# dmx-transciever.net
KiCad netlist of a schematic drawn in EAGLE
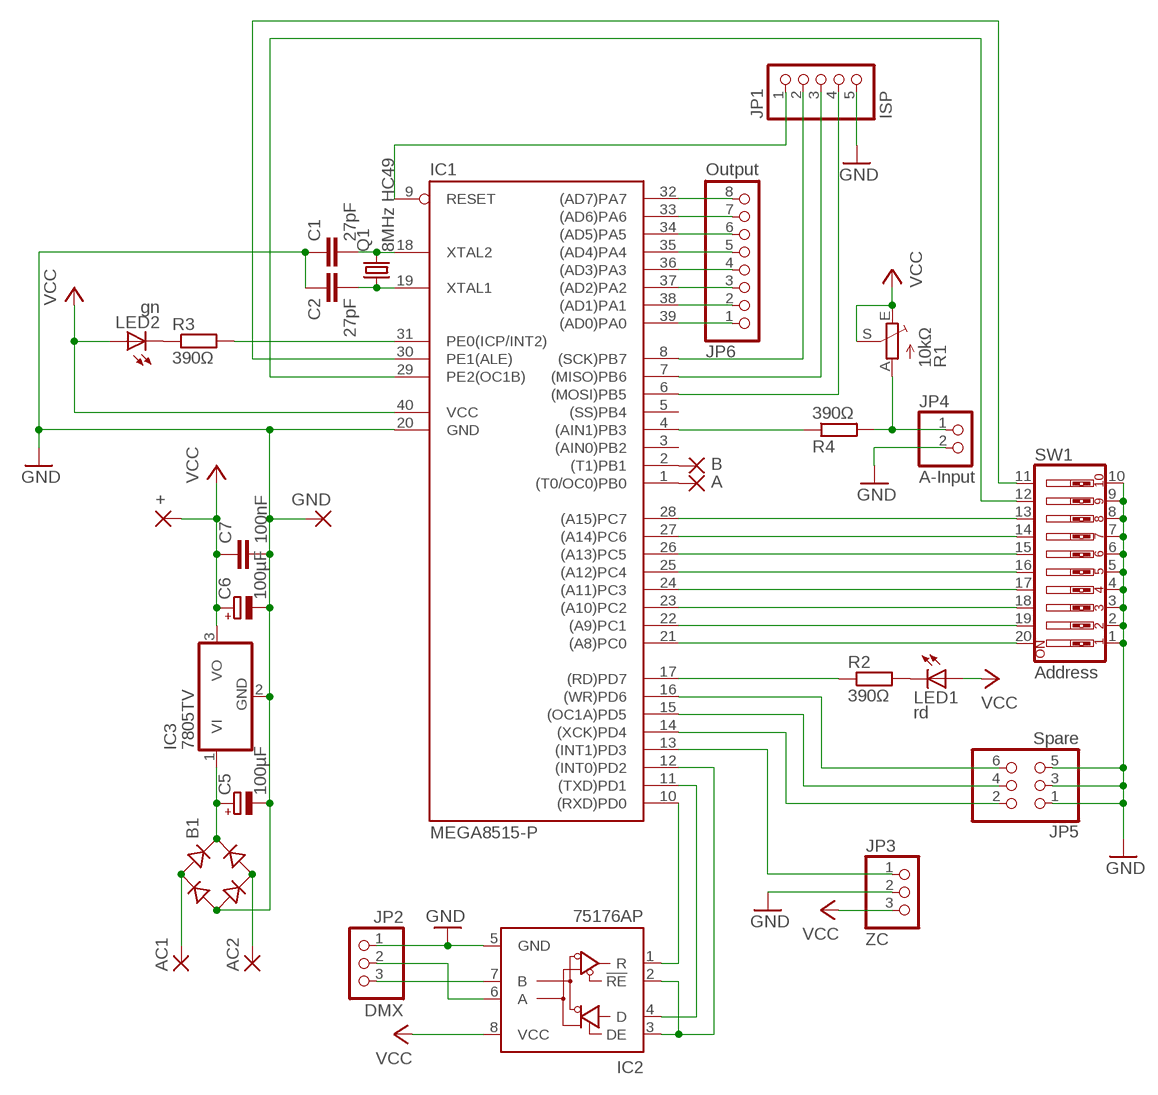
[diagram p0: schematic, sheet 1]

(export (version "E")
  (design (tool "Eeschema 10.0.6"))
  (components
    (comp (ref "+")
      (value "WIREPAD2,54/1,0")
      (footprint "eagle-import:2,54_1,0")
      (libsource (lib "eagle-import") (part "WIREPAD2,54/1,0"))
    )
    (comp (ref "A")
      (value "WIREPAD2,54/1,0")
      (footprint "eagle-import:2,54_1,0")
      (libsource (lib "eagle-import") (part "WIREPAD2,54/1,0"))
    )
    (comp (ref "AC1")
      (value "WIREPAD2,54/1,0")
      (footprint "eagle-import:2,54_1,0")
      (libsource (lib "eagle-import") (part "WIREPAD2,54/1,0"))
    )
    (comp (ref "AC2")
      (value "WIREPAD2,54/1,0")
      (footprint "eagle-import:2,54_1,0")
      (libsource (lib "eagle-import") (part "WIREPAD2,54/1,0"))
    )
    (comp (ref "B")
      (value "WIREPAD2,54/1,0")
      (footprint "eagle-import:2,54_1,0")
      (libsource (lib "eagle-import") (part "WIREPAD2,54/1,0"))
    )
    (comp (ref "B1")
      (value "RB1A")
      (footprint "eagle-import:RB1A")
      (libsource (lib "eagle-import") (part "RB1A"))
    )
    (comp (ref "C1")
      (value "27pF")
      (footprint "eagle-import:C050-024X044")
      (libsource (lib "eagle-import") (part "C-EU050-024X044"))
    )
    (comp (ref "C2")
      (value "27pF")
      (footprint "eagle-import:C050-024X044")
      (libsource (lib "eagle-import") (part "C-EU050-024X044"))
    )
    (comp (ref "C5")
      (value "100µF")
      (footprint "eagle-import:E2,5-7")
      (libsource (lib "eagle-import") (part "CPOL-EUE2.5-7"))
    )
    (comp (ref "C6")
      (value "100µF")
      (footprint "eagle-import:E2,5-7")
      (libsource (lib "eagle-import") (part "CPOL-EUE2.5-7"))
    )
    (comp (ref "C7")
      (value "100nF")
      (footprint "eagle-import:C050-024X044")
      (libsource (lib "eagle-import") (part "C-EU050-024X044"))
    )
    (comp (ref "GND")
      (value "WIREPAD2,54/1,0")
      (footprint "eagle-import:2,54_1,0")
      (libsource (lib "eagle-import") (part "WIREPAD2,54/1,0"))
    )
    (comp (ref "IC1")
      (value "MEGA8515-P")
      (footprint "eagle-import:DIL40")
      (libsource (lib "eagle-import") (part "MEGA8515-P"))
    )
    (comp (ref "IC2")
      (value "75176AP")
      (footprint "eagle-import:DIL08")
      (libsource (lib "eagle-import") (part "75176AP"))
    )
    (comp (ref "IC3")
      (value "7805TV")
      (footprint "eagle-import:TO220V")
      (libsource (lib "eagle-import") (part "78TV05"))
    )
    (comp (ref "JP1")
      (value "ISP")
      (footprint "eagle-import:1X05")
      (libsource (lib "eagle-import") (part "PINHD-1X5"))
    )
    (comp (ref "JP2")
      (value "DMX")
      (footprint "eagle-import:1X03")
      (libsource (lib "eagle-import") (part "PINHD-1X3"))
    )
    (comp (ref "JP3")
      (value "ZC")
      (footprint "eagle-import:1X03")
      (libsource (lib "eagle-import") (part "PINHD-1X3"))
    )
    (comp (ref "JP4")
      (value "A-Input")
      (footprint "eagle-import:1X02")
      (libsource (lib "eagle-import") (part "PINHD-1X2"))
    )
    (comp (ref "JP5")
      (value "Spare")
      (footprint "eagle-import:2X03")
      (libsource (lib "eagle-import") (part "PINHD-2X3"))
    )
    (comp (ref "JP6")
      (value "Output")
      (footprint "eagle-import:1X08")
      (libsource (lib "eagle-import") (part "PINHD-1X8"))
    )
    (comp (ref "LED1")
      (value "rd")
      (footprint "eagle-import:LED3MM")
      (fields (field (name "MF") "VISHAY SEMICONDUCTOR"))
      (libsource (lib "eagle-import") (part "TLLR4400"))
    )
    (comp (ref "LED2")
      (value "gn")
      (footprint "eagle-import:LED3MM")
      (fields (field (name "MF") "VISHAY SEMICONDUCTOR"))
      (libsource (lib "eagle-import") (part "TLLG4400"))
    )
    (comp (ref "Q1")
      (value "8MHz HC49")
      (footprint "eagle-import:HC49_S")
      (libsource (lib "eagle-import") (part "CRYSTALHC49S"))
    )
    (comp (ref "R1")
      (value "10kΩ")
      (footprint "eagle-import:PT-10S")
      (libsource (lib "eagle-import") (part "TRIM_EU-PT10S"))
    )
    (comp (ref "R2")
      (value "390Ω")
      (footprint "eagle-import:0207_10")
      (libsource (lib "eagle-import") (part "R-EU_0207/10"))
    )
    (comp (ref "R3")
      (value "390Ω")
      (footprint "eagle-import:0309V")
      (libsource (lib "eagle-import") (part "R-EU_0309/V"))
    )
    (comp (ref "R4")
      (value "390Ω")
      (footprint "eagle-import:0207_10")
      (libsource (lib "eagle-import") (part "R-EU_0207/10"))
    )
    (comp (ref "SW1")
      (value "Address")
      (footprint "eagle-import:EDG-10")
      (libsource (lib "eagle-import") (part "SW_DIP-10"))
    )
  )
  (nets
    (net (code "1") (name "GND") (class "Default")
      (node (ref "B1") (pin "-") (pinfunction "-_-") (pintype "passive"))
      (node (ref "C1") (pin "1") (pinfunction "1_1") (pintype "passive"))
      (node (ref "C2") (pin "1") (pinfunction "1_1") (pintype "passive"))
      (node (ref "C5") (pin "-") (pinfunction "-_-") (pintype "passive"))
      (node (ref "C6") (pin "-") (pinfunction "-_-") (pintype "passive"))
      (node (ref "C7") (pin "2") (pinfunction "2_2") (pintype "passive"))
      (node (ref "GND") (pin "1") (pinfunction "P_1") (pintype "passive"))
      (node (ref "IC1") (pin "20") (pinfunction "GND_20") (pintype "power_in"))
      (node (ref "IC2") (pin "5") (pinfunction "GND_5") (pintype "power_in"))
      (node (ref "IC3") (pin "2") (pinfunction "GND_2") (pintype "passive"))
      (node (ref "JP1") (pin "5") (pinfunction "5_5") (pintype "passive"))
      (node (ref "JP2") (pin "1") (pinfunction "1_1") (pintype "passive"))
      (node (ref "JP3") (pin "2") (pinfunction "2_2") (pintype "passive"))
      (node (ref "JP4") (pin "2") (pinfunction "2_2") (pintype "passive"))
      (node (ref "JP5") (pin "1") (pinfunction "1_1") (pintype "passive"))
      (node (ref "JP5") (pin "3") (pinfunction "3_3") (pintype "passive"))
      (node (ref "JP5") (pin "5") (pinfunction "5_5") (pintype "passive"))
      (node (ref "SW1") (pin "1") (pinfunction "1_1") (pintype "passive"))
      (node (ref "SW1") (pin "10") (pinfunction "10_10") (pintype "passive"))
      (node (ref "SW1") (pin "2") (pinfunction "2_2") (pintype "passive"))
      (node (ref "SW1") (pin "3") (pinfunction "3_3") (pintype "passive"))
      (node (ref "SW1") (pin "4") (pinfunction "4_4") (pintype "passive"))
      (node (ref "SW1") (pin "5") (pinfunction "5_5") (pintype "passive"))
      (node (ref "SW1") (pin "6") (pinfunction "6_6") (pintype "passive"))
      (node (ref "SW1") (pin "7") (pinfunction "7_7") (pintype "passive"))
      (node (ref "SW1") (pin "8") (pinfunction "8_8") (pintype "passive"))
      (node (ref "SW1") (pin "9") (pinfunction "9_9") (pintype "passive"))
    )
    (net (code "2") (name "Net-(A-P)") (class "Default")
      (node (ref "A") (pin "1") (pinfunction "P_1") (pintype "passive"))
      (node (ref "IC1") (pin "1") (pinfunction "(T0/OC0)PB0_1") (pintype "bidirectional"))
    )
    (net (code "3") (name "Net-(AC1-P)") (class "Default")
      (node (ref "AC1") (pin "1") (pinfunction "P_1") (pintype "passive"))
      (node (ref "B1") (pin "AC1") (pinfunction "AC1_AC1") (pintype "passive"))
    )
    (net (code "4") (name "Net-(AC2-P)") (class "Default")
      (node (ref "AC2") (pin "1") (pinfunction "P_1") (pintype "passive"))
      (node (ref "B1") (pin "AC2") (pinfunction "AC2_AC2") (pintype "passive"))
    )
    (net (code "5") (name "Net-(B-P)") (class "Default")
      (node (ref "B") (pin "1") (pinfunction "P_1") (pintype "passive"))
      (node (ref "IC1") (pin "2") (pinfunction "(T1)PB1_2") (pintype "bidirectional"))
    )
    (net (code "6") (name "Net-(IC1-(A8)PC0)") (class "Default")
      (node (ref "IC1") (pin "21") (pinfunction "(A8)PC0_21") (pintype "bidirectional"))
      (node (ref "SW1") (pin "20") (pinfunction "20_20") (pintype "passive"))
    )
    (net (code "7") (name "Net-(IC1-(A9)PC1)") (class "Default")
      (node (ref "IC1") (pin "22") (pinfunction "(A9)PC1_22") (pintype "bidirectional"))
      (node (ref "SW1") (pin "19") (pinfunction "19_19") (pintype "passive"))
    )
    (net (code "8") (name "Net-(IC1-(A10)PC2)") (class "Default")
      (node (ref "IC1") (pin "23") (pinfunction "(A10)PC2_23") (pintype "bidirectional"))
      (node (ref "SW1") (pin "18") (pinfunction "18_18") (pintype "passive"))
    )
    (net (code "9") (name "Net-(IC1-(A11)PC3)") (class "Default")
      (node (ref "IC1") (pin "24") (pinfunction "(A11)PC3_24") (pintype "bidirectional"))
      (node (ref "SW1") (pin "17") (pinfunction "17_17") (pintype "passive"))
    )
    (net (code "10") (name "Net-(IC1-(A12)PC4)") (class "Default")
      (node (ref "IC1") (pin "25") (pinfunction "(A12)PC4_25") (pintype "bidirectional"))
      (node (ref "SW1") (pin "16") (pinfunction "16_16") (pintype "passive"))
    )
    (net (code "11") (name "Net-(IC1-(A13)PC5)") (class "Default")
      (node (ref "IC1") (pin "26") (pinfunction "(A13)PC5_26") (pintype "bidirectional"))
      (node (ref "SW1") (pin "15") (pinfunction "15_15") (pintype "passive"))
    )
    (net (code "12") (name "Net-(IC1-(A14)PC6)") (class "Default")
      (node (ref "IC1") (pin "27") (pinfunction "(A14)PC6_27") (pintype "bidirectional"))
      (node (ref "SW1") (pin "14") (pinfunction "14_14") (pintype "passive"))
    )
    (net (code "13") (name "Net-(IC1-(A15)PC7)") (class "Default")
      (node (ref "IC1") (pin "28") (pinfunction "(A15)PC7_28") (pintype "bidirectional"))
      (node (ref "SW1") (pin "13") (pinfunction "13_13") (pintype "passive"))
    )
    (net (code "14") (name "Net-(IC1-(AD0)PA0)") (class "Default")
      (node (ref "IC1") (pin "39") (pinfunction "(AD0)PA0_39") (pintype "bidirectional"))
      (node (ref "JP6") (pin "1") (pinfunction "1_1") (pintype "passive"))
    )
    (net (code "15") (name "Net-(IC1-(AD1)PA1)") (class "Default")
      (node (ref "IC1") (pin "38") (pinfunction "(AD1)PA1_38") (pintype "bidirectional"))
      (node (ref "JP6") (pin "2") (pinfunction "2_2") (pintype "passive"))
    )
    (net (code "16") (name "Net-(IC1-(AD2)PA2)") (class "Default")
      (node (ref "IC1") (pin "37") (pinfunction "(AD2)PA2_37") (pintype "bidirectional"))
      (node (ref "JP6") (pin "3") (pinfunction "3_3") (pintype "passive"))
    )
    (net (code "17") (name "Net-(IC1-(AD3)PA3)") (class "Default")
      (node (ref "IC1") (pin "36") (pinfunction "(AD3)PA3_36") (pintype "bidirectional"))
      (node (ref "JP6") (pin "4") (pinfunction "4_4") (pintype "passive"))
    )
    (net (code "18") (name "Net-(IC1-(AD4)PA4)") (class "Default")
      (node (ref "IC1") (pin "35") (pinfunction "(AD4)PA4_35") (pintype "bidirectional"))
      (node (ref "JP6") (pin "5") (pinfunction "5_5") (pintype "passive"))
    )
    (net (code "19") (name "Net-(IC1-(AD5)PA5)") (class "Default")
      (node (ref "IC1") (pin "34") (pinfunction "(AD5)PA5_34") (pintype "bidirectional"))
      (node (ref "JP6") (pin "6") (pinfunction "6_6") (pintype "passive"))
    )
    (net (code "20") (name "Net-(IC1-(AD6)PA6)") (class "Default")
      (node (ref "IC1") (pin "33") (pinfunction "(AD6)PA6_33") (pintype "bidirectional"))
      (node (ref "JP6") (pin "7") (pinfunction "7_7") (pintype "passive"))
    )
    (net (code "21") (name "Net-(IC1-(AD7)PA7)") (class "Default")
      (node (ref "IC1") (pin "32") (pinfunction "(AD7)PA7_32") (pintype "bidirectional"))
      (node (ref "JP6") (pin "8") (pinfunction "8_8") (pintype "passive"))
    )
    (net (code "22") (name "Net-(IC1-(AIN1)PB3)") (class "Default")
      (node (ref "IC1") (pin "4") (pinfunction "(AIN1)PB3_4") (pintype "bidirectional"))
      (node (ref "R4") (pin "1") (pinfunction "1_1") (pintype "passive"))
    )
    (net (code "23") (name "Net-(IC1-(INT0)PD2)") (class "Default")
      (node (ref "IC1") (pin "12") (pinfunction "(INT0)PD2_12") (pintype "bidirectional"))
      (node (ref "IC2") (pin "2") (pinfunction "~{RE}_2") (pintype "input"))
      (node (ref "IC2") (pin "3") (pinfunction "DE_3") (pintype "input"))
    )
    (net (code "24") (name "Net-(IC1-(INT1)PD3)") (class "Default")
      (node (ref "IC1") (pin "13") (pinfunction "(INT1)PD3_13") (pintype "bidirectional"))
      (node (ref "JP3") (pin "1") (pinfunction "1_1") (pintype "passive"))
    )
    (net (code "25") (name "Net-(IC1-(MISO)PB6)") (class "Default")
      (node (ref "IC1") (pin "7") (pinfunction "(MISO)PB6_7") (pintype "bidirectional"))
      (node (ref "JP1") (pin "3") (pinfunction "3_3") (pintype "passive"))
    )
    (net (code "26") (name "Net-(IC1-(MOSI)PB5)") (class "Default")
      (node (ref "IC1") (pin "6") (pinfunction "(MOSI)PB5_6") (pintype "bidirectional"))
      (node (ref "JP1") (pin "4") (pinfunction "4_4") (pintype "passive"))
    )
    (net (code "27") (name "Net-(IC1-(OC1A)PD5)") (class "Default")
      (node (ref "IC1") (pin "15") (pinfunction "(OC1A)PD5_15") (pintype "bidirectional"))
      (node (ref "JP5") (pin "4") (pinfunction "4_4") (pintype "passive"))
    )
    (net (code "28") (name "Net-(IC1-(RD)PD7)") (class "Default")
      (node (ref "IC1") (pin "17") (pinfunction "(RD)PD7_17") (pintype "bidirectional"))
      (node (ref "R2") (pin "1") (pinfunction "1_1") (pintype "passive"))
    )
    (net (code "29") (name "Net-(IC1-(RXD)PD0)") (class "Default")
      (node (ref "IC1") (pin "10") (pinfunction "(RXD)PD0_10") (pintype "bidirectional"))
      (node (ref "IC2") (pin "1") (pinfunction "R_1") (pintype "input"))
    )
    (net (code "30") (name "Net-(IC1-(SCK)PB7)") (class "Default")
      (node (ref "IC1") (pin "8") (pinfunction "(SCK)PB7_8") (pintype "bidirectional"))
      (node (ref "JP1") (pin "2") (pinfunction "2_2") (pintype "passive"))
    )
    (net (code "31") (name "Net-(IC1-(TXD)PD1)") (class "Default")
      (node (ref "IC1") (pin "11") (pinfunction "(TXD)PD1_11") (pintype "bidirectional"))
      (node (ref "IC2") (pin "4") (pinfunction "D_4") (pintype "input"))
    )
    (net (code "32") (name "Net-(IC1-(WR)PD6)") (class "Default")
      (node (ref "IC1") (pin "16") (pinfunction "(WR)PD6_16") (pintype "bidirectional"))
      (node (ref "JP5") (pin "6") (pinfunction "6_6") (pintype "passive"))
    )
    (net (code "33") (name "Net-(IC1-(XCK)PD4)") (class "Default")
      (node (ref "IC1") (pin "14") (pinfunction "(XCK)PD4_14") (pintype "bidirectional"))
      (node (ref "JP5") (pin "2") (pinfunction "2_2") (pintype "passive"))
    )
    (net (code "34") (name "Net-(IC1-PE0(ICP{slash}INT2))") (class "Default")
      (node (ref "IC1") (pin "31") (pinfunction "PE0(ICP/INT2)_31") (pintype "bidirectional"))
      (node (ref "R3") (pin "2") (pinfunction "2_2") (pintype "passive"))
    )
    (net (code "35") (name "Net-(IC1-PE1(ALE))") (class "Default")
      (node (ref "IC1") (pin "30") (pinfunction "PE1(ALE)_30") (pintype "bidirectional"))
      (node (ref "SW1") (pin "11") (pinfunction "11_11") (pintype "passive"))
    )
    (net (code "36") (name "Net-(IC1-PE2(OC1B))") (class "Default")
      (node (ref "IC1") (pin "29") (pinfunction "PE2(OC1B)_29") (pintype "bidirectional"))
      (node (ref "SW1") (pin "12") (pinfunction "12_12") (pintype "passive"))
    )
    (net (code "37") (name "Net-(IC1-RESET)") (class "Default")
      (node (ref "IC1") (pin "9") (pinfunction "RESET_9") (pintype "input"))
      (node (ref "JP1") (pin "1") (pinfunction "1_1") (pintype "passive"))
    )
    (net (code "38") (name "Net-(IC1-XTAL1)") (class "Default")
      (node (ref "C2") (pin "2") (pinfunction "2_2") (pintype "passive"))
      (node (ref "IC1") (pin "19") (pinfunction "XTAL1_19") (pintype "bidirectional"))
      (node (ref "Q1") (pin "1") (pinfunction "1_1") (pintype "passive"))
    )
    (net (code "39") (name "Net-(IC1-XTAL2)") (class "Default")
      (node (ref "C1") (pin "2") (pinfunction "2_2") (pintype "passive"))
      (node (ref "IC1") (pin "18") (pinfunction "XTAL2_18") (pintype "bidirectional"))
      (node (ref "Q1") (pin "2") (pinfunction "2_2") (pintype "passive"))
    )
    (net (code "40") (name "Net-(IC2-A)") (class "Default")
      (node (ref "IC2") (pin "6") (pinfunction "A_6") (pintype "output"))
      (node (ref "JP2") (pin "2") (pinfunction "2_2") (pintype "passive"))
    )
    (net (code "41") (name "Net-(IC2-B)") (class "Default")
      (node (ref "IC2") (pin "7") (pinfunction "B_7") (pintype "output"))
      (node (ref "JP2") (pin "3") (pinfunction "3_3") (pintype "passive"))
    )
    (net (code "42") (name "Net-(IC3-VI)") (class "Default")
      (node (ref "B1") (pin "+") (pinfunction "+_+") (pintype "passive"))
      (node (ref "C5") (pin "+") (pinfunction "+_+") (pintype "passive"))
      (node (ref "IC3") (pin "1") (pinfunction "VI_1") (pintype "input"))
    )
    (net (code "43") (name "Net-(JP4-Pad1)") (class "Default")
      (node (ref "JP4") (pin "1") (pinfunction "1_1") (pintype "passive"))
      (node (ref "R1") (pin "A") (pinfunction "A_A") (pintype "passive"))
      (node (ref "R4") (pin "2") (pinfunction "2_2") (pintype "passive"))
    )
    (net (code "44") (name "Net-(LED1-C)") (class "Default")
      (node (ref "LED1") (pin "K") (pinfunction "C_K") (pintype "passive"))
      (node (ref "R2") (pin "2") (pinfunction "2_2") (pintype "passive"))
    )
    (net (code "45") (name "Net-(LED2-C)") (class "Default")
      (node (ref "LED2") (pin "K") (pinfunction "C_K") (pintype "passive"))
      (node (ref "R3") (pin "1") (pinfunction "1_1") (pintype "passive"))
    )
    (net (code "46") (name "VCC") (class "Default")
      (node (ref "+") (pin "1") (pinfunction "P_1") (pintype "passive"))
      (node (ref "C6") (pin "+") (pinfunction "+_+") (pintype "passive"))
      (node (ref "C7") (pin "1") (pinfunction "1_1") (pintype "passive"))
      (node (ref "IC1") (pin "40") (pinfunction "VCC_40") (pintype "power_in"))
      (node (ref "IC2") (pin "8") (pinfunction "VCC_8") (pintype "power_in"))
      (node (ref "IC3") (pin "3") (pinfunction "VO_3") (pintype "passive"))
      (node (ref "JP3") (pin "3") (pinfunction "3_3") (pintype "passive"))
      (node (ref "LED1") (pin "A") (pinfunction "A_A") (pintype "passive"))
      (node (ref "LED2") (pin "A") (pinfunction "A_A") (pintype "passive"))
      (node (ref "R1") (pin "E") (pinfunction "E_E") (pintype "passive"))
      (node (ref "R1") (pin "S") (pinfunction "S_S") (pintype "passive"))
    )
    (net (code "47") (name "unconnected-(IC1-(AIN0)PB2-Pad3)") (class "Default")
      (node (ref "IC1") (pin "3") (pinfunction "(AIN0)PB2_3") (pintype "bidirectional"))
    )
    (net (code "48") (name "unconnected-(IC1-(SS)PB4-Pad5)") (class "Default")
      (node (ref "IC1") (pin "5") (pinfunction "(SS)PB4_5") (pintype "bidirectional"))
    )
  )
)
